# FPGA_NonIO.net
KiCad netlist of a schematic drawn in Altium Designer
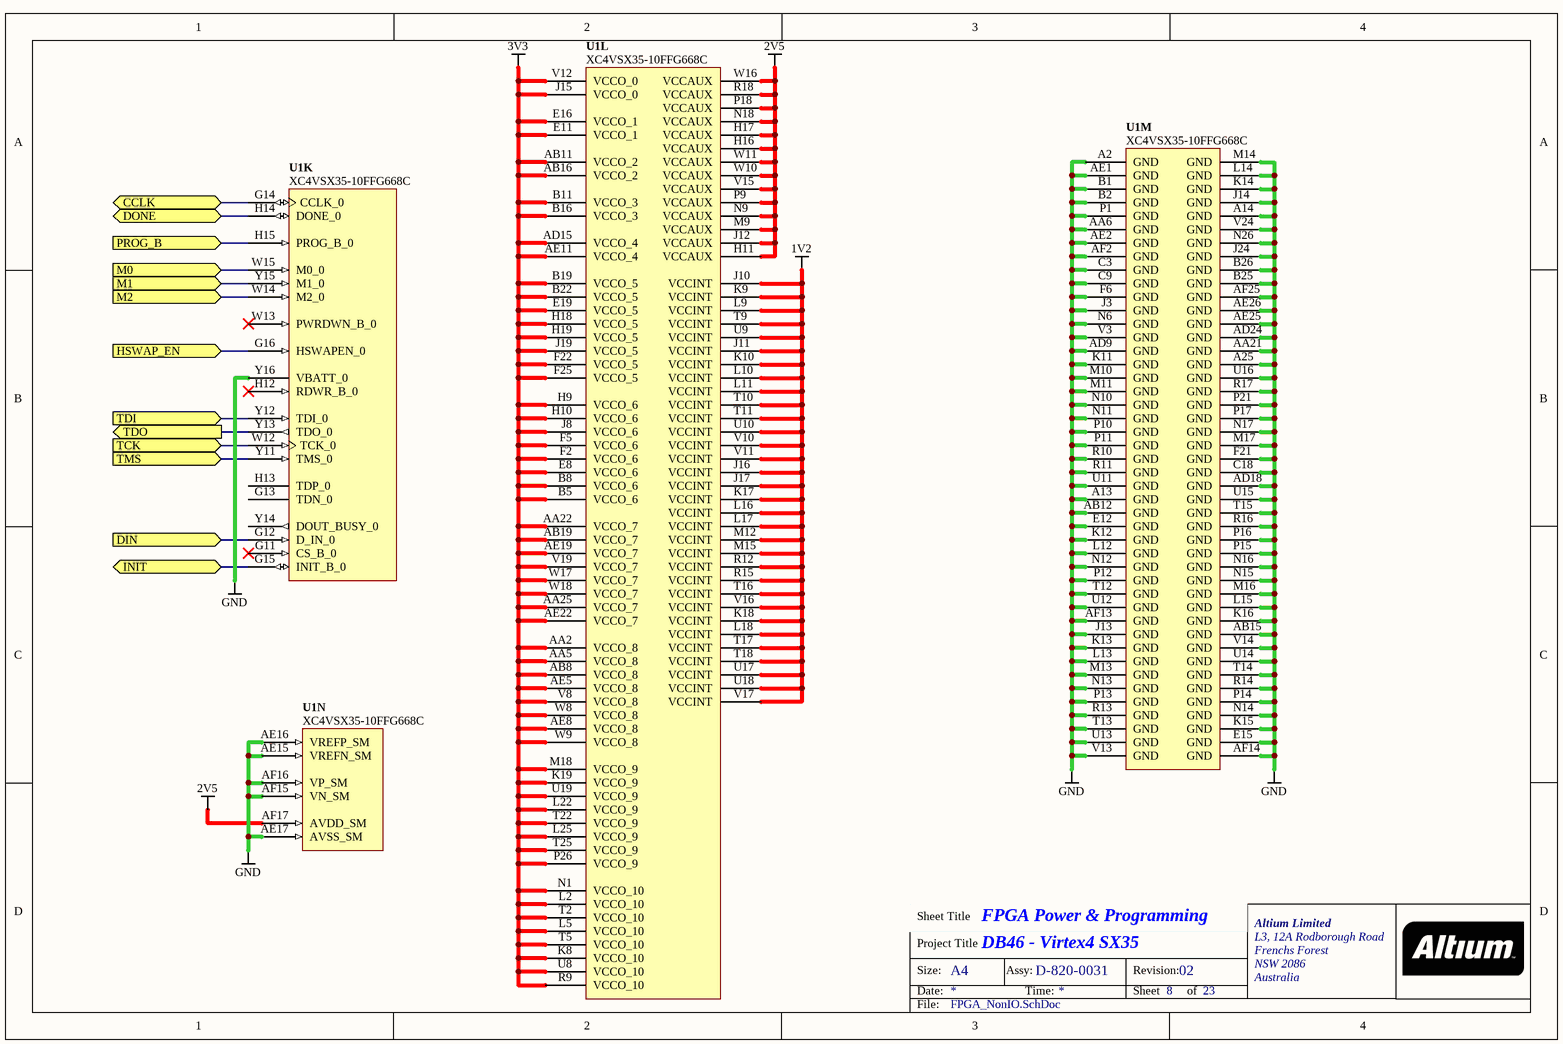
[diagram p0: FPGA_NonIO.SchDoc]

(export (version "E")
  (design (tool "Eeschema 10.0.6"))
  (components
    (comp (ref "U1")
      (value "XC4VSX35-10FFG668C")
      (footprint "XC4VLX25-10FF668C")
      (description "FPGA, Xilinx Virtex-4, XC4VSX35")
      (libsource (lib "AltiumDesignLibrary") (part "XC4VSX35-10FFG668C"))
    )
  )
  (nets
    (net (code "1") (name "/CCLK") (class "Default")
      (node (ref "U1") (pin "G14") (pinfunction "CCLK_0_G14") (pintype "bidirectional"))
    )
    (net (code "2") (name "/DIN") (class "Default")
      (node (ref "U1") (pin "G12") (pinfunction "D_IN_0_G12") (pintype "input"))
    )
    (net (code "3") (name "/DONE") (class "Default")
      (node (ref "U1") (pin "H14") (pinfunction "DONE_0_H14") (pintype "bidirectional"))
    )
    (net (code "4") (name "/HSWAP_EN") (class "Default")
      (node (ref "U1") (pin "G16") (pinfunction "HSWAPEN_0_G16") (pintype "input"))
    )
    (net (code "5") (name "/INIT") (class "Default")
      (node (ref "U1") (pin "G15") (pinfunction "INIT_B_0_G15") (pintype "bidirectional"))
    )
    (net (code "6") (name "/M0") (class "Default")
      (node (ref "U1") (pin "W15") (pinfunction "M0_0_W15") (pintype "input"))
    )
    (net (code "7") (name "/M1") (class "Default")
      (node (ref "U1") (pin "Y15") (pinfunction "M1_0_Y15") (pintype "input"))
    )
    (net (code "8") (name "/M2") (class "Default")
      (node (ref "U1") (pin "W14") (pinfunction "M2_0_W14") (pintype "input"))
    )
    (net (code "9") (name "/PROG_B") (class "Default")
      (node (ref "U1") (pin "H15") (pinfunction "PROG_B_0_H15") (pintype "input"))
    )
    (net (code "10") (name "/TCK") (class "Default")
      (node (ref "U1") (pin "W12") (pinfunction "TCK_0_W12") (pintype "input"))
    )
    (net (code "11") (name "/TDI") (class "Default")
      (node (ref "U1") (pin "Y12") (pinfunction "TDI_0_Y12") (pintype "input"))
    )
    (net (code "12") (name "/TDO") (class "Default")
      (node (ref "U1") (pin "Y13") (pinfunction "TDO_0_Y13") (pintype "output"))
    )
    (net (code "13") (name "/TMS") (class "Default")
      (node (ref "U1") (pin "Y11") (pinfunction "TMS_0_Y11") (pintype "input"))
    )
    (net (code "14") (name "1V2") (class "Default")
      (node (ref "U1") (pin "J10") (pinfunction "VCCINT_J10") (pintype "power_in"))
      (node (ref "U1") (pin "J11") (pinfunction "VCCINT_J11") (pintype "power_in"))
      (node (ref "U1") (pin "J16") (pinfunction "VCCINT_J16") (pintype "power_in"))
      (node (ref "U1") (pin "J17") (pinfunction "VCCINT_J17") (pintype "power_in"))
      (node (ref "U1") (pin "K10") (pinfunction "VCCINT_K10") (pintype "power_in"))
      (node (ref "U1") (pin "K17") (pinfunction "VCCINT_K17") (pintype "power_in"))
      (node (ref "U1") (pin "K18") (pinfunction "VCCINT_K18") (pintype "power_in"))
      (node (ref "U1") (pin "K9") (pinfunction "VCCINT_K9") (pintype "power_in"))
      (node (ref "U1") (pin "L10") (pinfunction "VCCINT_L10") (pintype "power_in"))
      (node (ref "U1") (pin "L11") (pinfunction "VCCINT_L11") (pintype "power_in"))
      (node (ref "U1") (pin "L16") (pinfunction "VCCINT_L16") (pintype "power_in"))
      (node (ref "U1") (pin "L17") (pinfunction "VCCINT_L17") (pintype "power_in"))
      (node (ref "U1") (pin "L18") (pinfunction "VCCINT_L18") (pintype "power_in"))
      (node (ref "U1") (pin "L9") (pinfunction "VCCINT_L9") (pintype "power_in"))
      (node (ref "U1") (pin "M12") (pinfunction "VCCINT_M12") (pintype "power_in"))
      (node (ref "U1") (pin "M15") (pinfunction "VCCINT_M15") (pintype "power_in"))
      (node (ref "U1") (pin "R12") (pinfunction "VCCINT_R12") (pintype "power_in"))
      (node (ref "U1") (pin "R15") (pinfunction "VCCINT_R15") (pintype "power_in"))
      (node (ref "U1") (pin "T10") (pinfunction "VCCINT_T10") (pintype "power_in"))
      (node (ref "U1") (pin "T11") (pinfunction "VCCINT_T11") (pintype "power_in"))
      (node (ref "U1") (pin "T16") (pinfunction "VCCINT_T16") (pintype "power_in"))
      (node (ref "U1") (pin "T17") (pinfunction "VCCINT_T17") (pintype "power_in"))
      (node (ref "U1") (pin "T18") (pinfunction "VCCINT_T18") (pintype "power_in"))
      (node (ref "U1") (pin "T9") (pinfunction "VCCINT_T9") (pintype "power_in"))
      (node (ref "U1") (pin "U10") (pinfunction "VCCINT_U10") (pintype "power_in"))
      (node (ref "U1") (pin "U17") (pinfunction "VCCINT_U17") (pintype "power_in"))
      (node (ref "U1") (pin "U18") (pinfunction "VCCINT_U18") (pintype "power_in"))
      (node (ref "U1") (pin "U9") (pinfunction "VCCINT_U9") (pintype "power_in"))
      (node (ref "U1") (pin "V10") (pinfunction "VCCINT_V10") (pintype "power_in"))
      (node (ref "U1") (pin "V11") (pinfunction "VCCINT_V11") (pintype "power_in"))
      (node (ref "U1") (pin "V16") (pinfunction "VCCINT_V16") (pintype "power_in"))
      (node (ref "U1") (pin "V17") (pinfunction "VCCINT_V17") (pintype "power_in"))
    )
    (net (code "15") (name "2V5") (class "Default")
      (node (ref "U1") (pin "AF17") (pinfunction "AVDD_SM_AF17") (pintype "input"))
      (node (ref "U1") (pin "H11") (pinfunction "VCCAUX_H11") (pintype "power_in"))
      (node (ref "U1") (pin "H16") (pinfunction "VCCAUX_H16") (pintype "power_in"))
      (node (ref "U1") (pin "H17") (pinfunction "VCCAUX_H17") (pintype "power_in"))
      (node (ref "U1") (pin "J12") (pinfunction "VCCAUX_J12") (pintype "power_in"))
      (node (ref "U1") (pin "M9") (pinfunction "VCCAUX_M9") (pintype "power_in"))
      (node (ref "U1") (pin "N18") (pinfunction "VCCAUX_N18") (pintype "power_in"))
      (node (ref "U1") (pin "N9") (pinfunction "VCCAUX_N9") (pintype "power_in"))
      (node (ref "U1") (pin "P18") (pinfunction "VCCAUX_P18") (pintype "power_in"))
      (node (ref "U1") (pin "P9") (pinfunction "VCCAUX_P9") (pintype "power_in"))
      (node (ref "U1") (pin "R18") (pinfunction "VCCAUX_R18") (pintype "power_in"))
      (node (ref "U1") (pin "V15") (pinfunction "VCCAUX_V15") (pintype "power_in"))
      (node (ref "U1") (pin "W10") (pinfunction "VCCAUX_W10") (pintype "power_in"))
      (node (ref "U1") (pin "W11") (pinfunction "VCCAUX_W11") (pintype "power_in"))
      (node (ref "U1") (pin "W16") (pinfunction "VCCAUX_W16") (pintype "power_in"))
    )
    (net (code "16") (name "3V3") (class "Default")
      (node (ref "U1") (pin "AA2") (pinfunction "VCCO_8_AA2") (pintype "power_in"))
      (node (ref "U1") (pin "AA22") (pinfunction "VCCO_7_AA22") (pintype "power_in"))
      (node (ref "U1") (pin "AA25") (pinfunction "VCCO_7_AA25") (pintype "power_in"))
      (node (ref "U1") (pin "AA5") (pinfunction "VCCO_8_AA5") (pintype "power_in"))
      (node (ref "U1") (pin "AB11") (pinfunction "VCCO_2_AB11") (pintype "power_in"))
      (node (ref "U1") (pin "AB16") (pinfunction "VCCO_2_AB16") (pintype "power_in"))
      (node (ref "U1") (pin "AB19") (pinfunction "VCCO_7_AB19") (pintype "power_in"))
      (node (ref "U1") (pin "AB8") (pinfunction "VCCO_8_AB8") (pintype "power_in"))
      (node (ref "U1") (pin "AD15") (pinfunction "VCCO_4_AD15") (pintype "power_in"))
      (node (ref "U1") (pin "AE11") (pinfunction "VCCO_4_AE11") (pintype "power_in"))
      (node (ref "U1") (pin "AE19") (pinfunction "VCCO_7_AE19") (pintype "power_in"))
      (node (ref "U1") (pin "AE22") (pinfunction "VCCO_7_AE22") (pintype "power_in"))
      (node (ref "U1") (pin "AE5") (pinfunction "VCCO_8_AE5") (pintype "power_in"))
      (node (ref "U1") (pin "AE8") (pinfunction "VCCO_8_AE8") (pintype "power_in"))
      (node (ref "U1") (pin "B11") (pinfunction "VCCO_3_B11") (pintype "power_in"))
      (node (ref "U1") (pin "B16") (pinfunction "VCCO_3_B16") (pintype "power_in"))
      (node (ref "U1") (pin "B19") (pinfunction "VCCO_5_B19") (pintype "power_in"))
      (node (ref "U1") (pin "B22") (pinfunction "VCCO_5_B22") (pintype "power_in"))
      (node (ref "U1") (pin "B5") (pinfunction "VCCO_6_B5") (pintype "power_in"))
      (node (ref "U1") (pin "B8") (pinfunction "VCCO_6_B8") (pintype "power_in"))
      (node (ref "U1") (pin "E11") (pinfunction "VCCO_1_E11") (pintype "power_in"))
      (node (ref "U1") (pin "E16") (pinfunction "VCCO_1_E16") (pintype "power_in"))
      (node (ref "U1") (pin "E19") (pinfunction "VCCO_5_E19") (pintype "power_in"))
      (node (ref "U1") (pin "E8") (pinfunction "VCCO_6_E8") (pintype "power_in"))
      (node (ref "U1") (pin "F2") (pinfunction "VCCO_6_F2") (pintype "power_in"))
      (node (ref "U1") (pin "F22") (pinfunction "VCCO_5_F22") (pintype "power_in"))
      (node (ref "U1") (pin "F25") (pinfunction "VCCO_5_F25") (pintype "power_in"))
      (node (ref "U1") (pin "F5") (pinfunction "VCCO_6_F5") (pintype "power_in"))
      (node (ref "U1") (pin "H10") (pinfunction "VCCO_6_H10") (pintype "power_in"))
      (node (ref "U1") (pin "H18") (pinfunction "VCCO_5_H18") (pintype "power_in"))
      (node (ref "U1") (pin "H19") (pinfunction "VCCO_5_H19") (pintype "power_in"))
      (node (ref "U1") (pin "H9") (pinfunction "VCCO_6_H9") (pintype "power_in"))
      (node (ref "U1") (pin "J15") (pinfunction "VCCO_0_J15") (pintype "power_in"))
      (node (ref "U1") (pin "J19") (pinfunction "VCCO_5_J19") (pintype "power_in"))
      (node (ref "U1") (pin "J8") (pinfunction "VCCO_6_J8") (pintype "power_in"))
      (node (ref "U1") (pin "K19") (pinfunction "VCCO_9_K19") (pintype "power_in"))
      (node (ref "U1") (pin "K8") (pinfunction "VCCO_10_K8") (pintype "power_in"))
      (node (ref "U1") (pin "L2") (pinfunction "VCCO_10_L2") (pintype "power_in"))
      (node (ref "U1") (pin "L22") (pinfunction "VCCO_9_L22") (pintype "power_in"))
      (node (ref "U1") (pin "L25") (pinfunction "VCCO_9_L25") (pintype "power_in"))
      (node (ref "U1") (pin "L5") (pinfunction "VCCO_10_L5") (pintype "power_in"))
      (node (ref "U1") (pin "M18") (pinfunction "VCCO_9_M18") (pintype "power_in"))
      (node (ref "U1") (pin "N1") (pinfunction "VCCO_10_N1") (pintype "power_in"))
      (node (ref "U1") (pin "P26") (pinfunction "VCCO_9_P26") (pintype "power_in"))
      (node (ref "U1") (pin "R9") (pinfunction "VCCO_10_R9") (pintype "power_in"))
      (node (ref "U1") (pin "T2") (pinfunction "VCCO_10_T2") (pintype "power_in"))
      (node (ref "U1") (pin "T22") (pinfunction "VCCO_9_T22") (pintype "power_in"))
      (node (ref "U1") (pin "T25") (pinfunction "VCCO_9_T25") (pintype "power_in"))
      (node (ref "U1") (pin "T5") (pinfunction "VCCO_10_T5") (pintype "power_in"))
      (node (ref "U1") (pin "U19") (pinfunction "VCCO_9_U19") (pintype "power_in"))
      (node (ref "U1") (pin "U8") (pinfunction "VCCO_10_U8") (pintype "power_in"))
      (node (ref "U1") (pin "V12") (pinfunction "VCCO_0_V12") (pintype "power_in"))
      (node (ref "U1") (pin "V19") (pinfunction "VCCO_7_V19") (pintype "power_in"))
      (node (ref "U1") (pin "V8") (pinfunction "VCCO_8_V8") (pintype "power_in"))
      (node (ref "U1") (pin "W17") (pinfunction "VCCO_7_W17") (pintype "power_in"))
      (node (ref "U1") (pin "W18") (pinfunction "VCCO_7_W18") (pintype "power_in"))
      (node (ref "U1") (pin "W8") (pinfunction "VCCO_8_W8") (pintype "power_in"))
      (node (ref "U1") (pin "W9") (pinfunction "VCCO_8_W9") (pintype "power_in"))
    )
    (net (code "17") (name "GND") (class "Default")
      (node (ref "U1") (pin "A13") (pinfunction "GND_A13") (pintype "power_in"))
      (node (ref "U1") (pin "A14") (pinfunction "GND_A14") (pintype "power_in"))
      (node (ref "U1") (pin "A2") (pinfunction "GND_A2") (pintype "power_in"))
      (node (ref "U1") (pin "A25") (pinfunction "GND_A25") (pintype "power_in"))
      (node (ref "U1") (pin "AA21") (pinfunction "GND_AA21") (pintype "power_in"))
      (node (ref "U1") (pin "AA6") (pinfunction "GND_AA6") (pintype "power_in"))
      (node (ref "U1") (pin "AB12") (pinfunction "GND_AB12") (pintype "power_in"))
      (node (ref "U1") (pin "AB15") (pinfunction "GND_AB15") (pintype "power_in"))
      (node (ref "U1") (pin "AD18") (pinfunction "GND_AD18") (pintype "power_in"))
      (node (ref "U1") (pin "AD24") (pinfunction "GND_AD24") (pintype "power_in"))
      (node (ref "U1") (pin "AD9") (pinfunction "GND_AD9") (pintype "power_in"))
      (node (ref "U1") (pin "AE1") (pinfunction "GND_AE1") (pintype "power_in"))
      (node (ref "U1") (pin "AE15") (pinfunction "VREFN_SM_AE15") (pintype "input"))
      (node (ref "U1") (pin "AE16") (pinfunction "VREFP_SM_AE16") (pintype "input"))
      (node (ref "U1") (pin "AE17") (pinfunction "AVSS_SM_AE17") (pintype "input"))
      (node (ref "U1") (pin "AE2") (pinfunction "GND_AE2") (pintype "power_in"))
      (node (ref "U1") (pin "AE25") (pinfunction "GND_AE25") (pintype "power_in"))
      (node (ref "U1") (pin "AE26") (pinfunction "GND_AE26") (pintype "power_in"))
      (node (ref "U1") (pin "AF13") (pinfunction "GND_AF13") (pintype "power_in"))
      (node (ref "U1") (pin "AF14") (pinfunction "GND_AF14") (pintype "power_in"))
      (node (ref "U1") (pin "AF15") (pinfunction "VN_SM_AF15") (pintype "input"))
      (node (ref "U1") (pin "AF16") (pinfunction "VP_SM_AF16") (pintype "input"))
      (node (ref "U1") (pin "AF2") (pinfunction "GND_AF2") (pintype "power_in"))
      (node (ref "U1") (pin "AF25") (pinfunction "GND_AF25") (pintype "power_in"))
      (node (ref "U1") (pin "B1") (pinfunction "GND_B1") (pintype "power_in"))
      (node (ref "U1") (pin "B2") (pinfunction "GND_B2") (pintype "power_in"))
      (node (ref "U1") (pin "B25") (pinfunction "GND_B25") (pintype "power_in"))
      (node (ref "U1") (pin "B26") (pinfunction "GND_B26") (pintype "power_in"))
      (node (ref "U1") (pin "C18") (pinfunction "GND_C18") (pintype "power_in"))
      (node (ref "U1") (pin "C3") (pinfunction "GND_C3") (pintype "power_in"))
      (node (ref "U1") (pin "C9") (pinfunction "GND_C9") (pintype "power_in"))
      (node (ref "U1") (pin "E12") (pinfunction "GND_E12") (pintype "power_in"))
      (node (ref "U1") (pin "E15") (pinfunction "GND_E15") (pintype "power_in"))
      (node (ref "U1") (pin "F21") (pinfunction "GND_F21") (pintype "power_in"))
      (node (ref "U1") (pin "F6") (pinfunction "GND_F6") (pintype "power_in"))
      (node (ref "U1") (pin "J13") (pinfunction "GND_J13") (pintype "power_in"))
      (node (ref "U1") (pin "J14") (pinfunction "GND_J14") (pintype "power_in"))
      (node (ref "U1") (pin "J24") (pinfunction "GND_J24") (pintype "power_in"))
      (node (ref "U1") (pin "J3") (pinfunction "GND_J3") (pintype "power_in"))
      (node (ref "U1") (pin "K11") (pinfunction "GND_K11") (pintype "power_in"))
      (node (ref "U1") (pin "K12") (pinfunction "GND_K12") (pintype "power_in"))
      (node (ref "U1") (pin "K13") (pinfunction "GND_K13") (pintype "power_in"))
      (node (ref "U1") (pin "K14") (pinfunction "GND_K14") (pintype "power_in"))
      (node (ref "U1") (pin "K15") (pinfunction "GND_K15") (pintype "power_in"))
      (node (ref "U1") (pin "K16") (pinfunction "GND_K16") (pintype "power_in"))
      (node (ref "U1") (pin "L12") (pinfunction "GND_L12") (pintype "power_in"))
      (node (ref "U1") (pin "L13") (pinfunction "GND_L13") (pintype "power_in"))
      (node (ref "U1") (pin "L14") (pinfunction "GND_L14") (pintype "power_in"))
      (node (ref "U1") (pin "L15") (pinfunction "GND_L15") (pintype "power_in"))
      (node (ref "U1") (pin "M10") (pinfunction "GND_M10") (pintype "power_in"))
      (node (ref "U1") (pin "M11") (pinfunction "GND_M11") (pintype "power_in"))
      (node (ref "U1") (pin "M13") (pinfunction "GND_M13") (pintype "power_in"))
      (node (ref "U1") (pin "M14") (pinfunction "GND_M14") (pintype "power_in"))
      (node (ref "U1") (pin "M16") (pinfunction "GND_M16") (pintype "power_in"))
      (node (ref "U1") (pin "M17") (pinfunction "GND_M17") (pintype "power_in"))
      (node (ref "U1") (pin "N10") (pinfunction "GND_N10") (pintype "power_in"))
      (node (ref "U1") (pin "N11") (pinfunction "GND_N11") (pintype "power_in"))
      (node (ref "U1") (pin "N12") (pinfunction "GND_N12") (pintype "power_in"))
      (node (ref "U1") (pin "N13") (pinfunction "GND_N13") (pintype "power_in"))
      (node (ref "U1") (pin "N14") (pinfunction "GND_N14") (pintype "power_in"))
      (node (ref "U1") (pin "N15") (pinfunction "GND_N15") (pintype "power_in"))
      (node (ref "U1") (pin "N16") (pinfunction "GND_N16") (pintype "power_in"))
      (node (ref "U1") (pin "N17") (pinfunction "GND_N17") (pintype "power_in"))
      (node (ref "U1") (pin "N26") (pinfunction "GND_N26") (pintype "power_in"))
      (node (ref "U1") (pin "N6") (pinfunction "GND_N6") (pintype "power_in"))
      (node (ref "U1") (pin "P1") (pinfunction "GND_P1") (pintype "power_in"))
      (node (ref "U1") (pin "P10") (pinfunction "GND_P10") (pintype "power_in"))
      (node (ref "U1") (pin "P11") (pinfunction "GND_P11") (pintype "power_in"))
      (node (ref "U1") (pin "P12") (pinfunction "GND_P12") (pintype "power_in"))
      (node (ref "U1") (pin "P13") (pinfunction "GND_P13") (pintype "power_in"))
      (node (ref "U1") (pin "P14") (pinfunction "GND_P14") (pintype "power_in"))
      (node (ref "U1") (pin "P15") (pinfunction "GND_P15") (pintype "power_in"))
      (node (ref "U1") (pin "P16") (pinfunction "GND_P16") (pintype "power_in"))
      (node (ref "U1") (pin "P17") (pinfunction "GND_P17") (pintype "power_in"))
      (node (ref "U1") (pin "P21") (pinfunction "GND_P21") (pintype "power_in"))
      (node (ref "U1") (pin "R10") (pinfunction "GND_R10") (pintype "power_in"))
      (node (ref "U1") (pin "R11") (pinfunction "GND_R11") (pintype "power_in"))
      (node (ref "U1") (pin "R13") (pinfunction "GND_R13") (pintype "power_in"))
      (node (ref "U1") (pin "R14") (pinfunction "GND_R14") (pintype "power_in"))
      (node (ref "U1") (pin "R16") (pinfunction "GND_R16") (pintype "power_in"))
      (node (ref "U1") (pin "R17") (pinfunction "GND_R17") (pintype "power_in"))
      (node (ref "U1") (pin "T12") (pinfunction "GND_T12") (pintype "power_in"))
      (node (ref "U1") (pin "T13") (pinfunction "GND_T13") (pintype "power_in"))
      (node (ref "U1") (pin "T14") (pinfunction "GND_T14") (pintype "power_in"))
      (node (ref "U1") (pin "T15") (pinfunction "GND_T15") (pintype "power_in"))
      (node (ref "U1") (pin "U11") (pinfunction "GND_U11") (pintype "power_in"))
      (node (ref "U1") (pin "U12") (pinfunction "GND_U12") (pintype "power_in"))
      (node (ref "U1") (pin "U13") (pinfunction "GND_U13") (pintype "power_in"))
      (node (ref "U1") (pin "U14") (pinfunction "GND_U14") (pintype "power_in"))
      (node (ref "U1") (pin "U15") (pinfunction "GND_U15") (pintype "power_in"))
      (node (ref "U1") (pin "U16") (pinfunction "GND_U16") (pintype "power_in"))
      (node (ref "U1") (pin "V13") (pinfunction "GND_V13") (pintype "power_in"))
      (node (ref "U1") (pin "V14") (pinfunction "GND_V14") (pintype "power_in"))
      (node (ref "U1") (pin "V24") (pinfunction "GND_V24") (pintype "power_in"))
      (node (ref "U1") (pin "V3") (pinfunction "GND_V3") (pintype "power_in"))
      (node (ref "U1") (pin "Y16") (pinfunction "VBATT_0_Y16") (pintype "power_in"))
    )
    (net (code "18") (name "unconnected-(U1K-CS_B_0-PadG11)") (class "Default")
      (node (ref "U1") (pin "G11") (pinfunction "CS_B_0_G11") (pintype "input+no_connect"))
    )
    (net (code "19") (name "unconnected-(U1K-DOUT_BUSY_0-PadY14)") (class "Default")
      (node (ref "U1") (pin "Y14") (pinfunction "DOUT_BUSY_0_Y14") (pintype "output"))
    )
    (net (code "20") (name "unconnected-(U1K-PWRDWN_B_0-PadW13)") (class "Default")
      (node (ref "U1") (pin "W13") (pinfunction "PWRDWN_B_0_W13") (pintype "input+no_connect"))
    )
    (net (code "21") (name "unconnected-(U1K-RDWR_B_0-PadH12)") (class "Default")
      (node (ref "U1") (pin "H12") (pinfunction "RDWR_B_0_H12") (pintype "input+no_connect"))
    )
    (net (code "22") (name "unconnected-(U1K-TDN_0-PadG13)") (class "Default")
      (node (ref "U1") (pin "G13") (pinfunction "TDN_0_G13") (pintype "passive"))
    )
    (net (code "23") (name "unconnected-(U1K-TDP_0-PadH13)") (class "Default")
      (node (ref "U1") (pin "H13") (pinfunction "TDP_0_H13") (pintype "passive"))
    )
  )
)
